# blue.net
KiCad netlist of a schematic drawn in Altium Designer
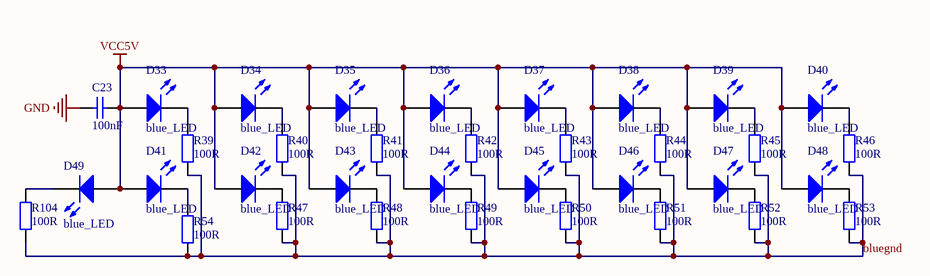
[diagram p0: blue.SchDoc]

(export (version "E")
  (design (tool "Eeschema 10.0.6"))
  (components
    (comp (ref "C23")
      (value "100nF")
      (footprint "CC2012-0805")
      (description "Capacitor (Semiconductor SIM Model)")
      (fields (field (name "PUBLISHER") "Altium Limited"))
      (libsource (lib "Motorcontrol2.0") (part "Cap Semi"))
    )
    (comp (ref "D33")
      (value "blue_LED")
      (footprint "LED5MM")
      (description "Typical RED GaAs LED")
      (fields (field (name "PUBLISHER") "Altium Limited"))
      (libsource (lib "Robocon_BJT") (part "LED"))
    )
    (comp (ref "D34")
      (value "blue_LED")
      (footprint "LED5MM")
      (description "Typical RED GaAs LED")
      (fields (field (name "PUBLISHER") "Altium Limited"))
      (libsource (lib "Robocon_BJT") (part "LED"))
    )
    (comp (ref "D35")
      (value "blue_LED")
      (footprint "LED5MM")
      (description "Typical RED GaAs LED")
      (fields (field (name "PUBLISHER") "Altium Limited"))
      (libsource (lib "Robocon_BJT") (part "LED"))
    )
    (comp (ref "D36")
      (value "blue_LED")
      (footprint "LED5MM")
      (description "Typical RED GaAs LED")
      (fields (field (name "PUBLISHER") "Altium Limited"))
      (libsource (lib "Robocon_BJT") (part "LED"))
    )
    (comp (ref "D37")
      (value "blue_LED")
      (footprint "LED5MM")
      (description "Typical RED GaAs LED")
      (fields (field (name "PUBLISHER") "Altium Limited"))
      (libsource (lib "Robocon_BJT") (part "LED"))
    )
    (comp (ref "D38")
      (value "blue_LED")
      (footprint "LED5MM")
      (description "Typical RED GaAs LED")
      (fields (field (name "PUBLISHER") "Altium Limited"))
      (libsource (lib "Robocon_BJT") (part "LED"))
    )
    (comp (ref "D39")
      (value "blue_LED")
      (footprint "LED5MM")
      (description "Typical RED GaAs LED")
      (fields (field (name "PUBLISHER") "Altium Limited"))
      (libsource (lib "Robocon_BJT") (part "LED"))
    )
    (comp (ref "D40")
      (value "blue_LED")
      (footprint "LED5MM")
      (description "Typical RED GaAs LED")
      (fields (field (name "PUBLISHER") "Altium Limited"))
      (libsource (lib "Robocon_BJT") (part "LED"))
    )
    (comp (ref "D41")
      (value "blue_LED")
      (footprint "LED5MM")
      (description "Typical RED GaAs LED")
      (fields (field (name "PUBLISHER") "Altium Limited"))
      (libsource (lib "Robocon_BJT") (part "LED"))
    )
    (comp (ref "D42")
      (value "blue_LED")
      (footprint "LED5MM")
      (description "Typical RED GaAs LED")
      (fields (field (name "PUBLISHER") "Altium Limited"))
      (libsource (lib "Robocon_BJT") (part "LED"))
    )
    (comp (ref "D43")
      (value "blue_LED")
      (footprint "LED5MM")
      (description "Typical RED GaAs LED")
      (fields (field (name "PUBLISHER") "Altium Limited"))
      (libsource (lib "Robocon_BJT") (part "LED"))
    )
    (comp (ref "D44")
      (value "blue_LED")
      (footprint "LED5MM")
      (description "Typical RED GaAs LED")
      (fields (field (name "PUBLISHER") "Altium Limited"))
      (libsource (lib "Robocon_BJT") (part "LED"))
    )
    (comp (ref "D45")
      (value "blue_LED")
      (footprint "LED5MM")
      (description "Typical RED GaAs LED")
      (fields (field (name "PUBLISHER") "Altium Limited"))
      (libsource (lib "Robocon_BJT") (part "LED"))
    )
    (comp (ref "D46")
      (value "blue_LED")
      (footprint "LED5MM")
      (description "Typical RED GaAs LED")
      (fields (field (name "PUBLISHER") "Altium Limited"))
      (libsource (lib "Robocon_BJT") (part "LED"))
    )
    (comp (ref "D47")
      (value "blue_LED")
      (footprint "LED5MM")
      (description "Typical RED GaAs LED")
      (fields (field (name "PUBLISHER") "Altium Limited"))
      (libsource (lib "Robocon_BJT") (part "LED"))
    )
    (comp (ref "D48")
      (value "blue_LED")
      (footprint "LED5MM")
      (description "Typical RED GaAs LED")
      (fields (field (name "PUBLISHER") "Altium Limited"))
      (libsource (lib "Robocon_BJT") (part "LED"))
    )
    (comp (ref "D49")
      (value "blue_LED")
      (footprint "LED5MM")
      (description "Typical RED GaAs LED")
      (fields (field (name "PUBLISHER") "Altium Limited"))
      (libsource (lib "Robocon_BJT") (part "LED"))
    )
    (comp (ref "R39")
      (value "100R")
      (footprint "CR2012-0805")
      (description "Resistor")
      (fields (field (name "PUBLISHER") "Altium Limited"))
      (libsource (lib "Robocon_RCL") (part "Res2"))
    )
    (comp (ref "R40")
      (value "100R")
      (footprint "CR2012-0805")
      (description "Resistor")
      (fields (field (name "PUBLISHER") "Altium Limited"))
      (libsource (lib "Robocon_RCL") (part "Res2"))
    )
    (comp (ref "R41")
      (value "100R")
      (footprint "CR2012-0805")
      (description "Resistor")
      (fields (field (name "PUBLISHER") "Altium Limited"))
      (libsource (lib "Robocon_RCL") (part "Res2"))
    )
    (comp (ref "R42")
      (value "100R")
      (footprint "CR2012-0805")
      (description "Resistor")
      (fields (field (name "PUBLISHER") "Altium Limited"))
      (libsource (lib "Robocon_RCL") (part "Res2"))
    )
    (comp (ref "R43")
      (value "100R")
      (footprint "CR2012-0805")
      (description "Resistor")
      (fields (field (name "PUBLISHER") "Altium Limited"))
      (libsource (lib "Robocon_RCL") (part "Res2"))
    )
    (comp (ref "R44")
      (value "100R")
      (footprint "CR2012-0805")
      (description "Resistor")
      (fields (field (name "PUBLISHER") "Altium Limited"))
      (libsource (lib "Robocon_RCL") (part "Res2"))
    )
    (comp (ref "R45")
      (value "100R")
      (footprint "CR2012-0805")
      (description "Resistor")
      (fields (field (name "PUBLISHER") "Altium Limited"))
      (libsource (lib "Robocon_RCL") (part "Res2"))
    )
    (comp (ref "R46")
      (value "100R")
      (footprint "CR2012-0805")
      (description "Resistor")
      (fields (field (name "PUBLISHER") "Altium Limited"))
      (libsource (lib "Robocon_RCL") (part "Res2"))
    )
    (comp (ref "R47")
      (value "100R")
      (footprint "CR2012-0805")
      (description "Resistor")
      (fields (field (name "PUBLISHER") "Altium Limited"))
      (libsource (lib "Robocon_RCL") (part "Res2"))
    )
    (comp (ref "R48")
      (value "100R")
      (footprint "CR2012-0805")
      (description "Resistor")
      (fields (field (name "PUBLISHER") "Altium Limited"))
      (libsource (lib "Robocon_RCL") (part "Res2"))
    )
    (comp (ref "R49")
      (value "100R")
      (footprint "CR2012-0805")
      (description "Resistor")
      (fields (field (name "PUBLISHER") "Altium Limited"))
      (libsource (lib "Robocon_RCL") (part "Res2"))
    )
    (comp (ref "R50")
      (value "100R")
      (footprint "CR2012-0805")
      (description "Resistor")
      (fields (field (name "PUBLISHER") "Altium Limited"))
      (libsource (lib "Robocon_RCL") (part "Res2"))
    )
    (comp (ref "R51")
      (value "100R")
      (footprint "CR2012-0805")
      (description "Resistor")
      (fields (field (name "PUBLISHER") "Altium Limited"))
      (libsource (lib "Robocon_RCL") (part "Res2"))
    )
    (comp (ref "R52")
      (value "100R")
      (footprint "CR2012-0805")
      (description "Resistor")
      (fields (field (name "PUBLISHER") "Altium Limited"))
      (libsource (lib "Robocon_RCL") (part "Res2"))
    )
    (comp (ref "R53")
      (value "100R")
      (footprint "CR2012-0805")
      (description "Resistor")
      (fields (field (name "PUBLISHER") "Altium Limited"))
      (libsource (lib "Robocon_RCL") (part "Res2"))
    )
    (comp (ref "R54")
      (value "100R")
      (footprint "CR2012-0805")
      (description "Resistor")
      (fields (field (name "PUBLISHER") "Altium Limited"))
      (libsource (lib "Robocon_RCL") (part "Res2"))
    )
    (comp (ref "R104")
      (value "100R")
      (footprint "CR2012-0805")
      (description "Resistor")
      (fields (field (name "PUBLISHER") "Altium Limited"))
      (libsource (lib "Robocon_RCL") (part "Res2"))
    )
  )
  (nets
    (net (code "1") (name "/bluegnd") (class "Default")
      (node (ref "R104") (pin "1") (pinfunction "1_1") (pintype "passive"))
      (node (ref "R39") (pin "1") (pinfunction "1_1") (pintype "passive"))
      (node (ref "R40") (pin "1") (pinfunction "1_1") (pintype "passive"))
      (node (ref "R41") (pin "1") (pinfunction "1_1") (pintype "passive"))
      (node (ref "R42") (pin "1") (pinfunction "1_1") (pintype "passive"))
      (node (ref "R43") (pin "1") (pinfunction "1_1") (pintype "passive"))
      (node (ref "R44") (pin "1") (pinfunction "1_1") (pintype "passive"))
      (node (ref "R45") (pin "1") (pinfunction "1_1") (pintype "passive"))
      (node (ref "R46") (pin "1") (pinfunction "1_1") (pintype "passive"))
      (node (ref "R47") (pin "1") (pinfunction "1_1") (pintype "passive"))
      (node (ref "R48") (pin "1") (pinfunction "1_1") (pintype "passive"))
      (node (ref "R49") (pin "1") (pinfunction "1_1") (pintype "passive"))
      (node (ref "R50") (pin "1") (pinfunction "1_1") (pintype "passive"))
      (node (ref "R51") (pin "1") (pinfunction "1_1") (pintype "passive"))
      (node (ref "R52") (pin "1") (pinfunction "1_1") (pintype "passive"))
      (node (ref "R53") (pin "1") (pinfunction "1_1") (pintype "passive"))
      (node (ref "R54") (pin "1") (pinfunction "1_1") (pintype "passive"))
    )
    (net (code "2") (name "GND") (class "Default")
      (node (ref "C23") (pin "2") (pinfunction "2_2") (pintype "passive"))
    )
    (net (code "3") (name "Net-(D33-K)") (class "Default")
      (node (ref "D33") (pin "2") (pinfunction "K_2") (pintype "passive"))
      (node (ref "R39") (pin "2") (pinfunction "2_2") (pintype "passive"))
    )
    (net (code "4") (name "Net-(D34-K)") (class "Default")
      (node (ref "D34") (pin "2") (pinfunction "K_2") (pintype "passive"))
      (node (ref "R40") (pin "2") (pinfunction "2_2") (pintype "passive"))
    )
    (net (code "5") (name "Net-(D35-K)") (class "Default")
      (node (ref "D35") (pin "2") (pinfunction "K_2") (pintype "passive"))
      (node (ref "R41") (pin "2") (pinfunction "2_2") (pintype "passive"))
    )
    (net (code "6") (name "Net-(D36-K)") (class "Default")
      (node (ref "D36") (pin "2") (pinfunction "K_2") (pintype "passive"))
      (node (ref "R42") (pin "2") (pinfunction "2_2") (pintype "passive"))
    )
    (net (code "7") (name "Net-(D37-K)") (class "Default")
      (node (ref "D37") (pin "2") (pinfunction "K_2") (pintype "passive"))
      (node (ref "R43") (pin "2") (pinfunction "2_2") (pintype "passive"))
    )
    (net (code "8") (name "Net-(D38-K)") (class "Default")
      (node (ref "D38") (pin "2") (pinfunction "K_2") (pintype "passive"))
      (node (ref "R44") (pin "2") (pinfunction "2_2") (pintype "passive"))
    )
    (net (code "9") (name "Net-(D39-K)") (class "Default")
      (node (ref "D39") (pin "2") (pinfunction "K_2") (pintype "passive"))
      (node (ref "R45") (pin "2") (pinfunction "2_2") (pintype "passive"))
    )
    (net (code "10") (name "Net-(D40-K)") (class "Default")
      (node (ref "D40") (pin "2") (pinfunction "K_2") (pintype "passive"))
      (node (ref "R46") (pin "2") (pinfunction "2_2") (pintype "passive"))
    )
    (net (code "11") (name "Net-(D41-K)") (class "Default")
      (node (ref "D41") (pin "2") (pinfunction "K_2") (pintype "passive"))
      (node (ref "R54") (pin "2") (pinfunction "2_2") (pintype "passive"))
    )
    (net (code "12") (name "Net-(D42-K)") (class "Default")
      (node (ref "D42") (pin "2") (pinfunction "K_2") (pintype "passive"))
      (node (ref "R47") (pin "2") (pinfunction "2_2") (pintype "passive"))
    )
    (net (code "13") (name "Net-(D43-K)") (class "Default")
      (node (ref "D43") (pin "2") (pinfunction "K_2") (pintype "passive"))
      (node (ref "R48") (pin "2") (pinfunction "2_2") (pintype "passive"))
    )
    (net (code "14") (name "Net-(D44-K)") (class "Default")
      (node (ref "D44") (pin "2") (pinfunction "K_2") (pintype "passive"))
      (node (ref "R49") (pin "2") (pinfunction "2_2") (pintype "passive"))
    )
    (net (code "15") (name "Net-(D45-K)") (class "Default")
      (node (ref "D45") (pin "2") (pinfunction "K_2") (pintype "passive"))
      (node (ref "R50") (pin "2") (pinfunction "2_2") (pintype "passive"))
    )
    (net (code "16") (name "Net-(D46-K)") (class "Default")
      (node (ref "D46") (pin "2") (pinfunction "K_2") (pintype "passive"))
      (node (ref "R51") (pin "2") (pinfunction "2_2") (pintype "passive"))
    )
    (net (code "17") (name "Net-(D47-K)") (class "Default")
      (node (ref "D47") (pin "2") (pinfunction "K_2") (pintype "passive"))
      (node (ref "R52") (pin "2") (pinfunction "2_2") (pintype "passive"))
    )
    (net (code "18") (name "Net-(D48-K)") (class "Default")
      (node (ref "D48") (pin "2") (pinfunction "K_2") (pintype "passive"))
      (node (ref "R53") (pin "2") (pinfunction "2_2") (pintype "passive"))
    )
    (net (code "19") (name "Net-(D49-K)") (class "Default")
      (node (ref "D49") (pin "2") (pinfunction "K_2") (pintype "passive"))
      (node (ref "R104") (pin "2") (pinfunction "2_2") (pintype "passive"))
    )
    (net (code "20") (name "VCC5V") (class "Default")
      (node (ref "C23") (pin "1") (pinfunction "1_1") (pintype "passive"))
      (node (ref "D33") (pin "1") (pinfunction "A_1") (pintype "passive"))
      (node (ref "D34") (pin "1") (pinfunction "A_1") (pintype "passive"))
      (node (ref "D35") (pin "1") (pinfunction "A_1") (pintype "passive"))
      (node (ref "D36") (pin "1") (pinfunction "A_1") (pintype "passive"))
      (node (ref "D37") (pin "1") (pinfunction "A_1") (pintype "passive"))
      (node (ref "D38") (pin "1") (pinfunction "A_1") (pintype "passive"))
      (node (ref "D39") (pin "1") (pinfunction "A_1") (pintype "passive"))
      (node (ref "D40") (pin "1") (pinfunction "A_1") (pintype "passive"))
      (node (ref "D41") (pin "1") (pinfunction "A_1") (pintype "passive"))
      (node (ref "D42") (pin "1") (pinfunction "A_1") (pintype "passive"))
      (node (ref "D43") (pin "1") (pinfunction "A_1") (pintype "passive"))
      (node (ref "D44") (pin "1") (pinfunction "A_1") (pintype "passive"))
      (node (ref "D45") (pin "1") (pinfunction "A_1") (pintype "passive"))
      (node (ref "D46") (pin "1") (pinfunction "A_1") (pintype "passive"))
      (node (ref "D47") (pin "1") (pinfunction "A_1") (pintype "passive"))
      (node (ref "D48") (pin "1") (pinfunction "A_1") (pintype "passive"))
      (node (ref "D49") (pin "1") (pinfunction "A_1") (pintype "passive"))
    )
  )
)
